# design.net
KiCad netlist of a schematic drawn in Altium Designer
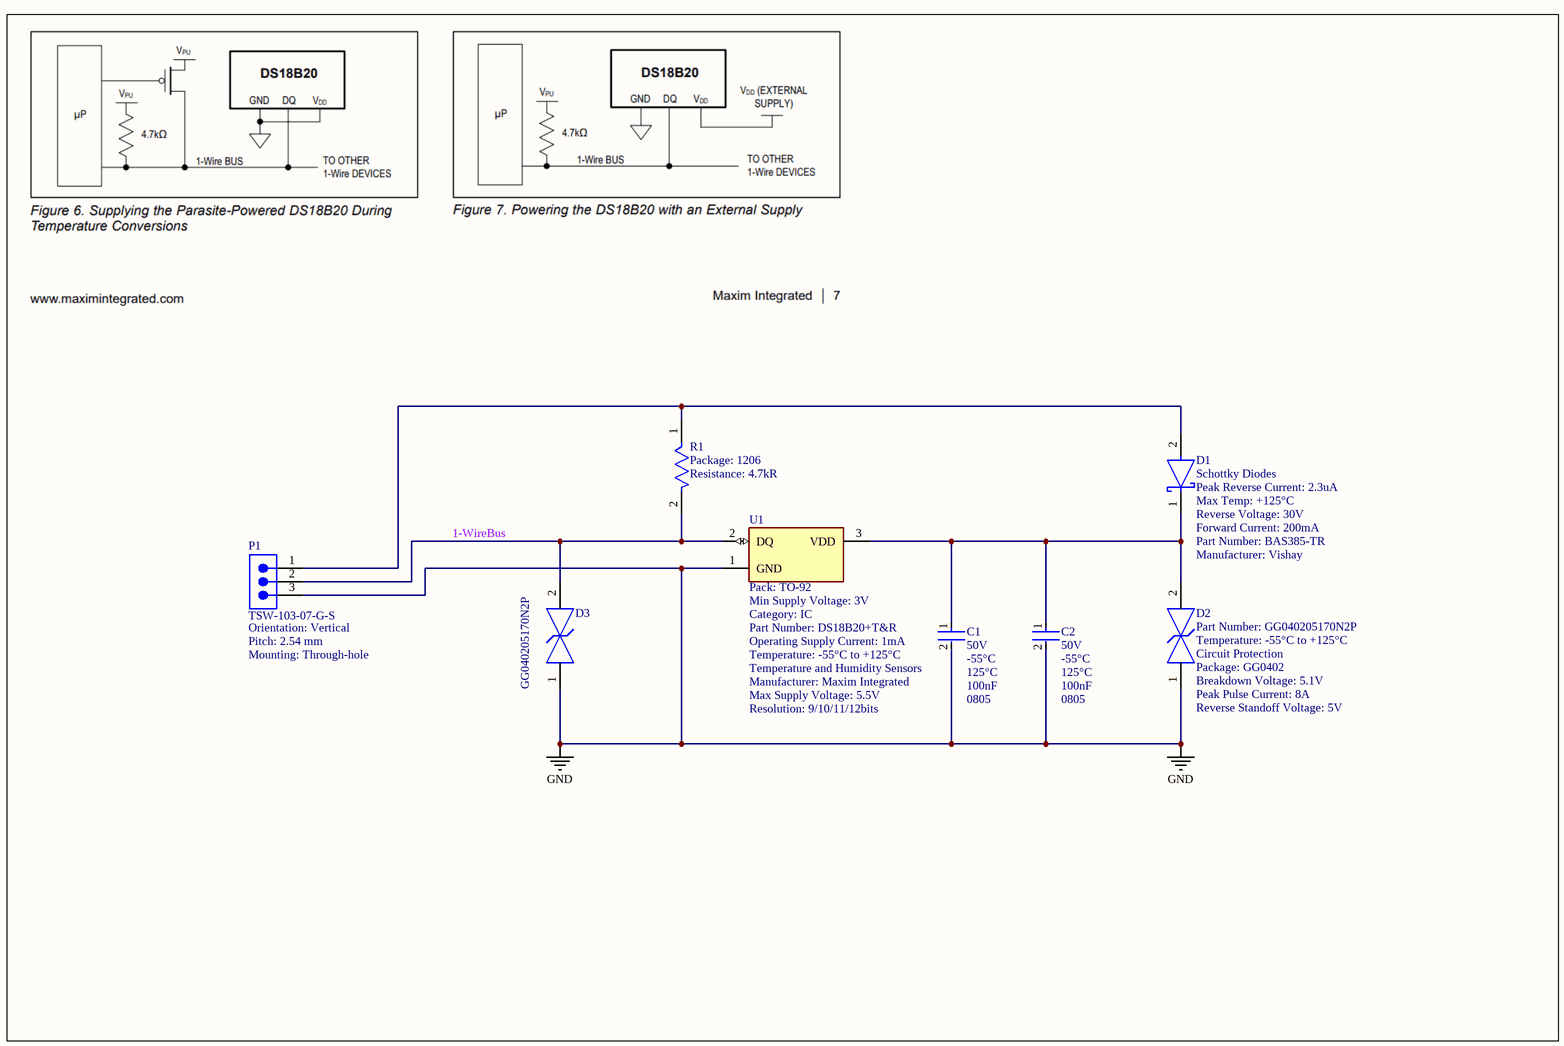
[diagram p0: Архитектура.SchDoc]

(export (version "E")
  (design (tool "Eeschema 10.0.6"))
  (components
    (comp (ref "C1")
      (value "GCD21BR71H104KA01L")
      (footprint "FP-GCD21B-0_15-IPC_C")
      (description "Chip Multilayer Ceramic Capacitors for Automotive, 0805, 0.10uF, X7R, 15%, 10%, 50V, Grade 1")
      (fields
        (field (name "VOLTAGE RATING") "50V")
        (field (name "MIN OPERATING TEMPERATURE") "-55°C")
        (field (name "MAX OPERATING TEMPERATURE") "125°C")
        (field (name "CAPACITANCE") "100nF")
        (field (name "CASE CODE (IMPERIAL)") "0805")
        (field (name "TOLERANCE") "10%")
      )
      (libsource (lib "Altium Content Vault") (part "b4654b650e69147ec39a6b967a45e02"))
    )
    (comp (ref "C2")
      (value "GCD21BR71H104KA01L")
      (footprint "FP-GCD21B-0_15-IPC_C")
      (description "Chip Multilayer Ceramic Capacitors for Automotive, 0805, 0.10uF, X7R, 15%, 10%, 50V, Grade 1")
      (fields
        (field (name "VOLTAGE RATING") "50V")
        (field (name "MIN OPERATING TEMPERATURE") "-55°C")
        (field (name "MAX OPERATING TEMPERATURE") "125°C")
        (field (name "CAPACITANCE") "100nF")
        (field (name "CASE CODE (IMPERIAL)") "0805")
        (field (name "TOLERANCE") "10%")
      )
      (libsource (lib "Altium Content Vault") (part "b4654b650e69147ec39a6b967a45e02"))
    )
    (comp (ref "D1")
      (value "BAS385-TR")
      (footprint "FP-6_560-5007_01-4-MFG")
      (description "Diode Schottky 30V 200mA Surface Mount MicroMELF")
      (fields
        (field (name "DEVICE CLASS L3") "Schottky Diodes")
        (field (name "PEAK REVERSE CURRENT") "2.3uA")
        (field (name "MAX TEMP") "+125°C")
        (field (name "REVERSE VOLTAGE") "30V")
        (field (name "OCTOPART") "https://octopart.com/bas385-tr-vishay-55507548")
        (field (name "FORWARD CURRENT") "200mA")
        (field (name "PART NUMBER") "BAS385-TR")
        (field (name "MANUFACTURER") "Vishay")
      )
      (libsource (lib "Altium Content Vault") (part "1d6ec82d83fb6aee721767c19dac4b9"))
    )
    (comp (ref "D2")
      (value "GG040205170N2P")
      (footprint "FP-GG0402-MFG")
      (description "TVS DIODE 5V 10V 0402")
      (fields
        (field (name "PART NUMBER") "GG040205170N2P")
        (field (name "TEMPERATURE") "-55°C to +125°C")
        (field (name "OCTOPART") "https://octopart.com/gg040205170n2p-avx-81066082")
        (field (name "MANUFACTURER") "AVX")
        (field (name "DEVICE CLASS L1") "Circuit Protection")
        (field (name "PACKAGE") "GG0402")
        (field (name "BREAKDOWN VOLTAGE") "5.1V")
        (field (name "PEAK PULSE CURRENT") "8A")
        (field (name "REVERSE STANDOFF VOLTAGE") "5V")
      )
      (libsource (lib "Altium Content Vault") (part "11bd9d59d340f0612179daf16ad9b72"))
    )
    (comp (ref "D3")
      (value "GG040205170N2P")
      (footprint "FP-GG0402-MFG")
      (description "TVS DIODE 5V 10V 0402")
      (fields
        (field (name "PART NUMBER") "GG040205170N2P")
        (field (name "OCTOPART") "https://octopart.com/gg040205170n2p-avx-81066082")
        (field (name "MANUFACTURER") "AVX")
      )
      (libsource (lib "Altium Content Vault") (part "11bd9d59d340f0612179daf16ad9b72"))
    )
    (comp (ref "P1")
      (value "TSW-103-07-G-S")
      (footprint "SMTC-TSW-103-07-X-S")
      (description "0.025\" SQ Post Header, Through-hole, Vertical, -55 to 125 degC, 2.54 mm Pitch, 3-Pin, Male, RoHS")
      (fields
        (field (name "MANUFACTURER") "Samtec")
        (field (name "ORIENTATION") "Vertical")
        (field (name "PITCH") "2.54 mm")
        (field (name "MOUNTING") "Through-hole")
      )
      (libsource (lib "Altium Content Vault") (part "SMTC-TSW-103-X-X-S-X"))
    )
    (comp (ref "R1")
      (value "RC3216F472CS")
      (footprint "FP-RC3216-IPC_A")
      (description "Res Thick Film 1206 4.7kΩ 1% 0.25W ±100ppm/°C Molded SMD T/R")
      (fields
        (field (name "PACKAGE") "1206")
        (field (name "TOLERANCE") "1%")
        (field (name "RESISTANCE") "4.7kR")
      )
      (libsource (lib "Altium Content Vault") (part "1029c3af85768c4190bb7ad29bc67b5"))
    )
    (comp (ref "U1")
      (value "DS18B20+T&R")
      (footprint "FP-Q3-4-MFG")
      (description "Temperature Sensor Digital, Local -55°C ~ 125°C 12 b TO-92-3")
      (fields
        (field (name "PACK") "TO-92")
        (field (name "MIN SUPPLY VOLTAGE") "3V")
        (field (name "OCTOPART") "https://octopart.com/ds18b20%2Bt%26r-maxim+integrated-10547047")
        (field (name "CATEGORY") "IC")
        (field (name "PART NUMBER") "DS18B20+T&R")
        (field (name "OPERATING SUPPLY CURRENT") "1mA")
        (field (name "TEMPERATURE") "-55°C to +125°C")
        (field (name "DEVICE CLASS L2") "Temperature and Humidity Sensors")
        (field (name "MANUFACTURER") "Maxim Integrated")
        (field (name "MAX SUPPLY VOLTAGE") "5.5V")
        (field (name "RESOLUTION") "9/10/11/12bits")
      )
      (libsource (lib "Altium Content Vault") (part "e4eb22da2d5f2b096fc4053ffedf8c8"))
    )
  )
  (nets
    (net (code "1") (name "/1-WireBus") (class "Default")
      (node (ref "D3") (pin "2") (pinfunction "2_2") (pintype "passive"))
      (node (ref "P1") (pin "2") (pinfunction "2_2") (pintype "passive"))
      (node (ref "R1") (pin "2") (pinfunction "2_2") (pintype "passive"))
      (node (ref "U1") (pin "2") (pinfunction "DQ_2") (pintype "bidirectional"))
    )
    (net (code "2") (name "GND") (class "Default")
      (node (ref "C1") (pin "2") (pinfunction "2_2") (pintype "passive"))
      (node (ref "C2") (pin "2") (pinfunction "2_2") (pintype "passive"))
      (node (ref "D2") (pin "1") (pinfunction "1_1") (pintype "passive"))
      (node (ref "D3") (pin "1") (pinfunction "1_1") (pintype "passive"))
      (node (ref "P1") (pin "3") (pinfunction "3_3") (pintype "passive"))
      (node (ref "U1") (pin "1") (pinfunction "GND_1") (pintype "power_in"))
    )
    (net (code "3") (name "Net-(D1-A)") (class "Default")
      (node (ref "D1") (pin "2") (pinfunction "A_2") (pintype "passive"))
      (node (ref "P1") (pin "1") (pinfunction "1_1") (pintype "passive"))
      (node (ref "R1") (pin "1") (pinfunction "1_1") (pintype "passive"))
    )
    (net (code "4") (name "Net-(D1-C)") (class "Default")
      (node (ref "C1") (pin "1") (pinfunction "1_1") (pintype "passive"))
      (node (ref "C2") (pin "1") (pinfunction "1_1") (pintype "passive"))
      (node (ref "D1") (pin "1") (pinfunction "C_1") (pintype "passive"))
      (node (ref "D2") (pin "2") (pinfunction "2_2") (pintype "passive"))
      (node (ref "U1") (pin "3") (pinfunction "VDD_3") (pintype "power_in"))
    )
  )
)
